# Draft0.net
KiCad netlist of a schematic drawn in EAGLE
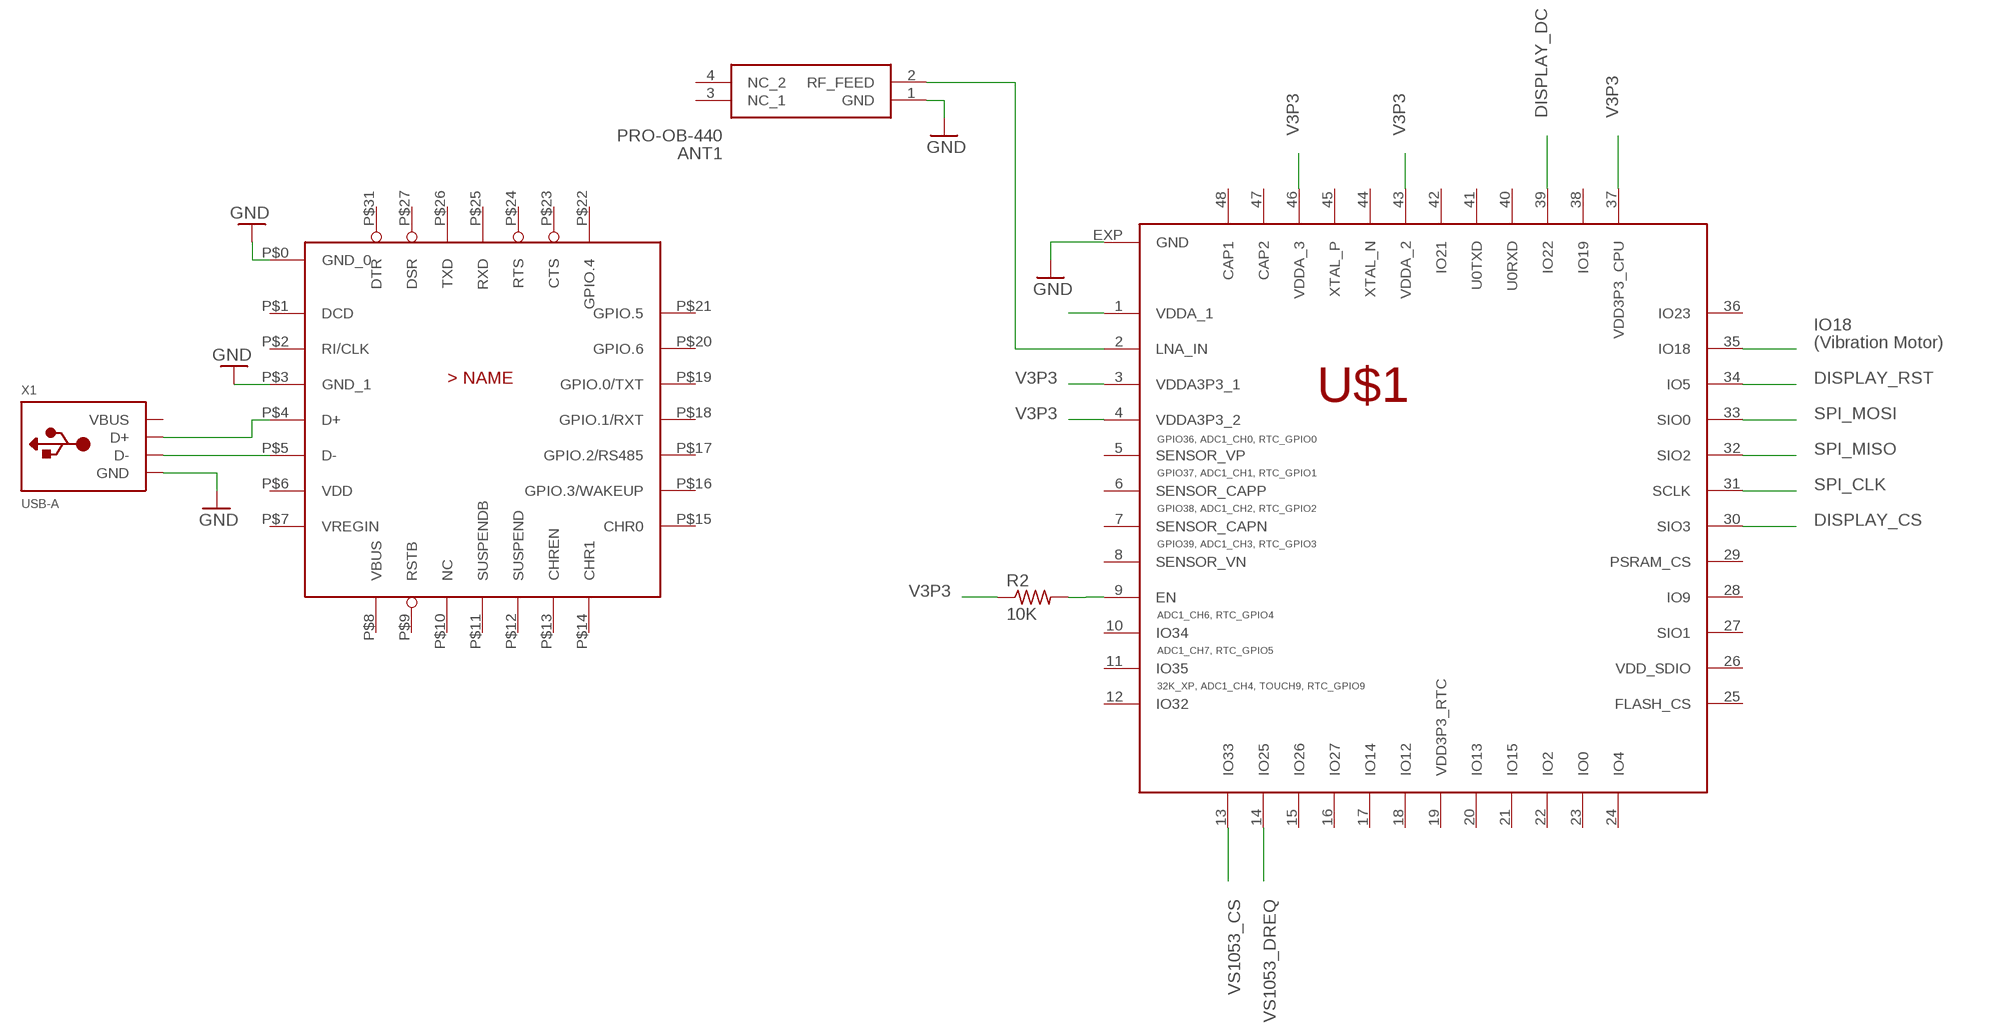
[diagram p0: schematic, sheet 1]
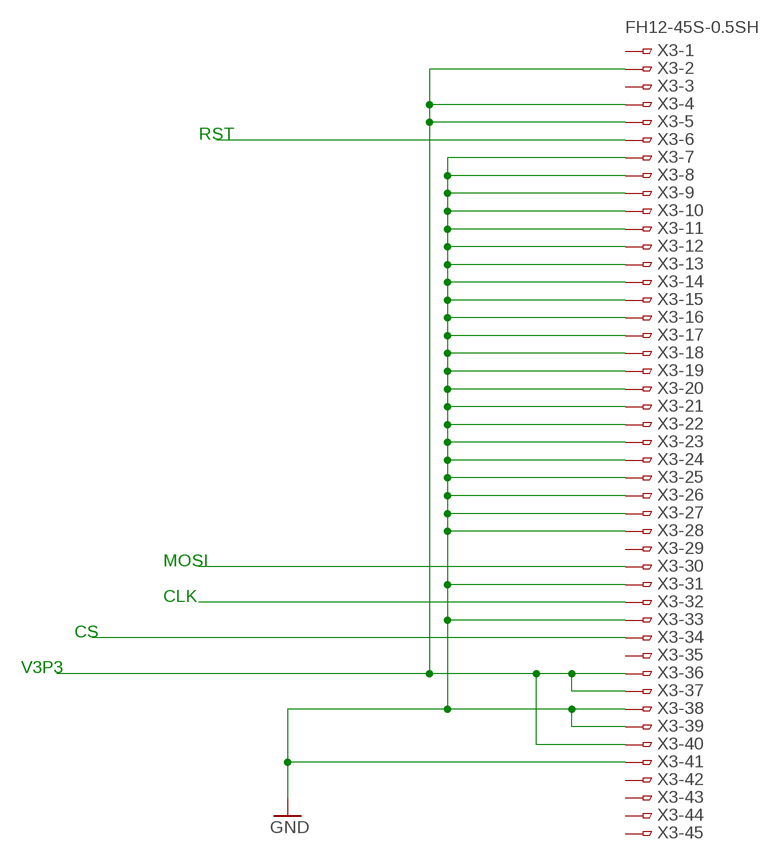
[diagram p1: schematic, sheet 2]
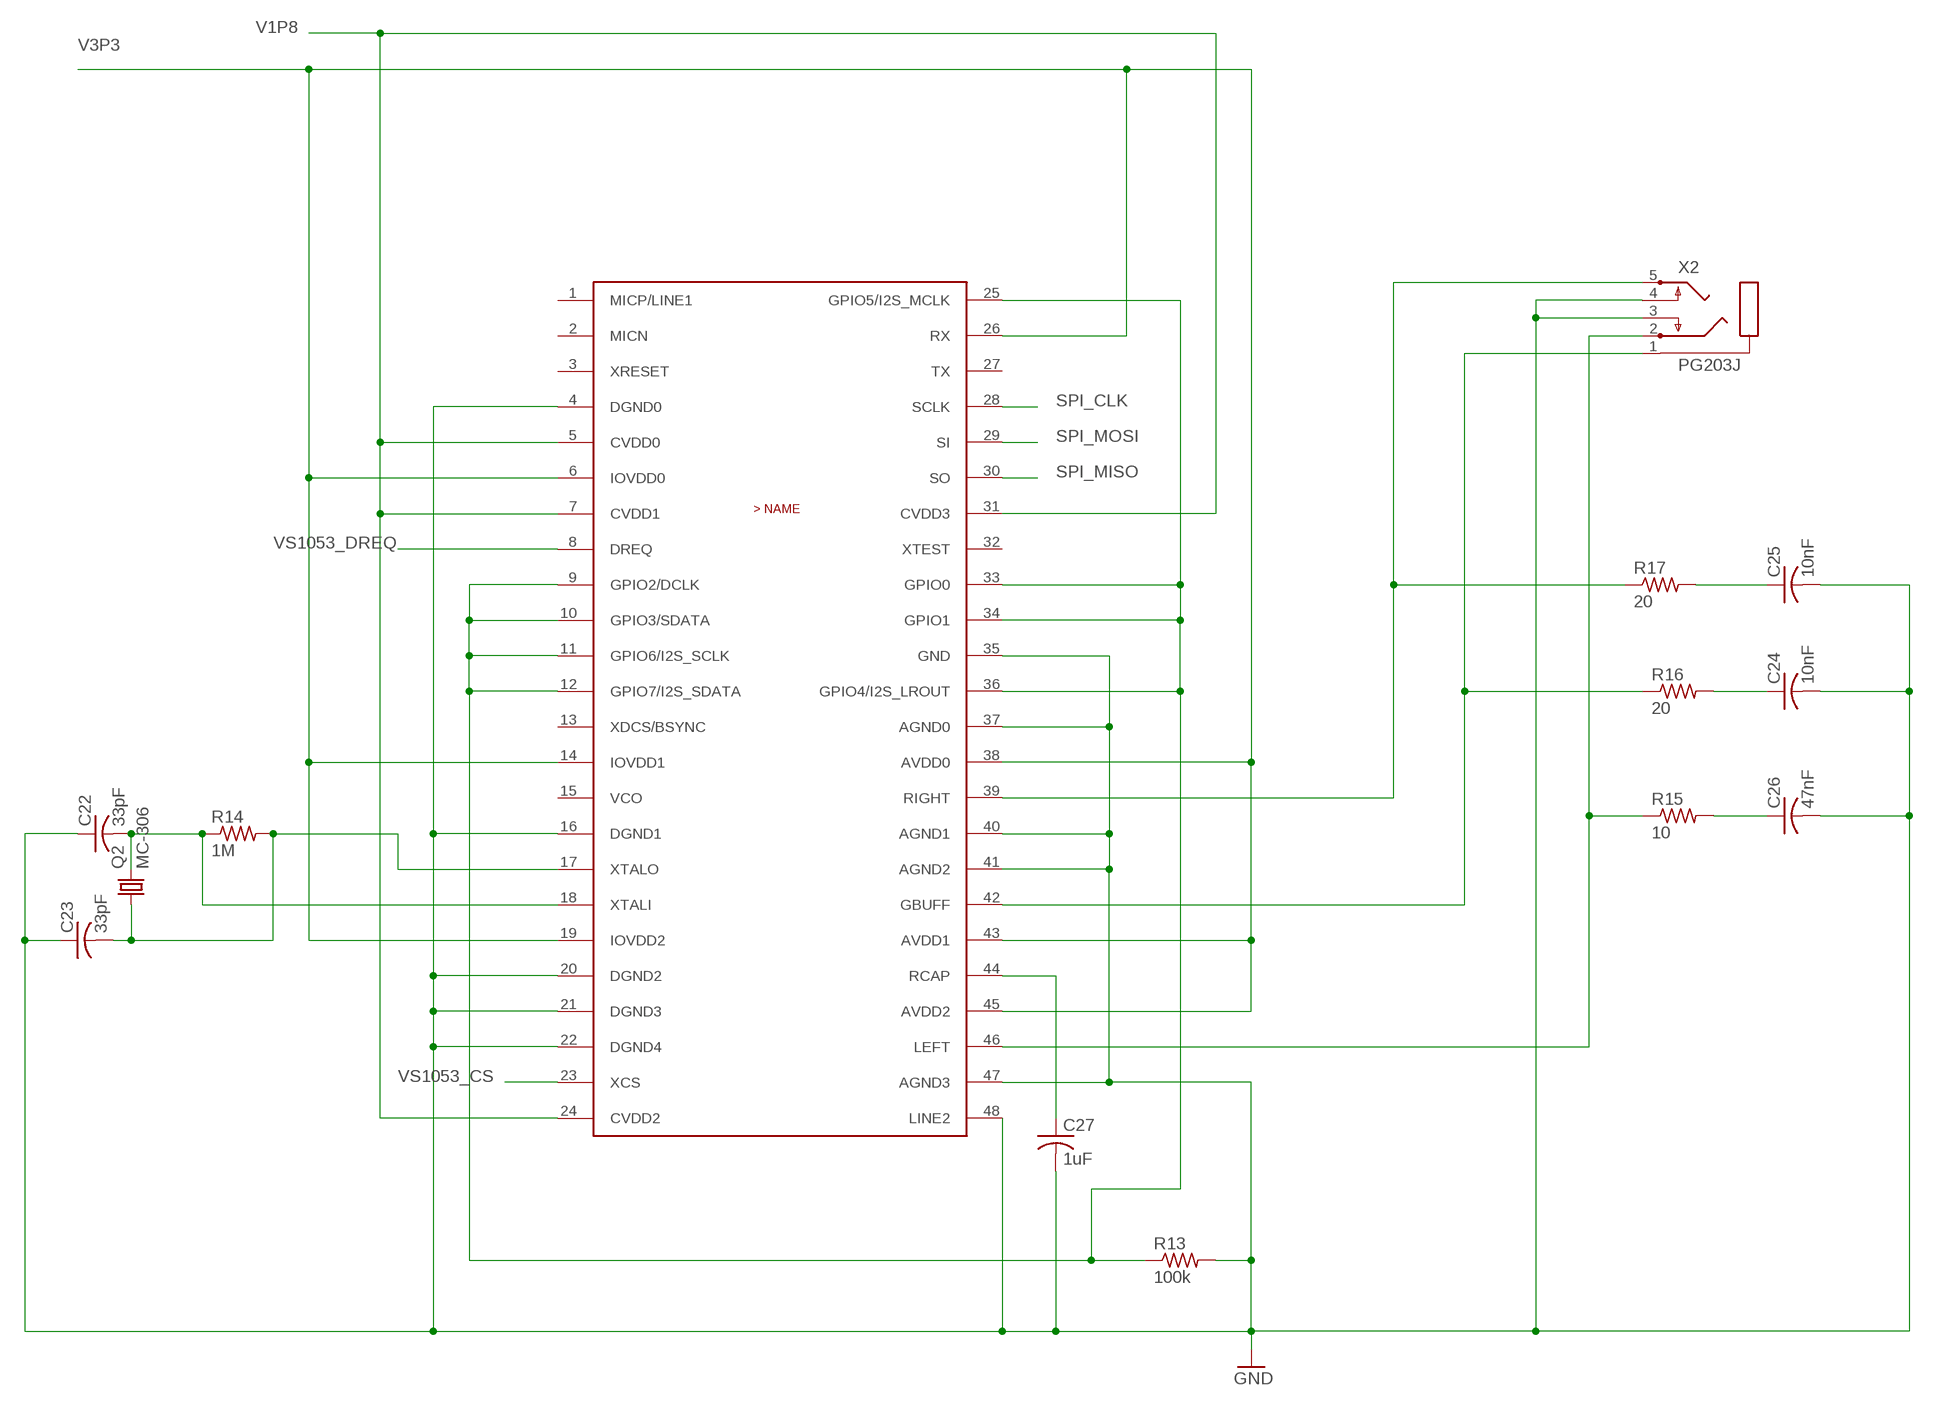
[diagram p2: schematic, sheet 3]
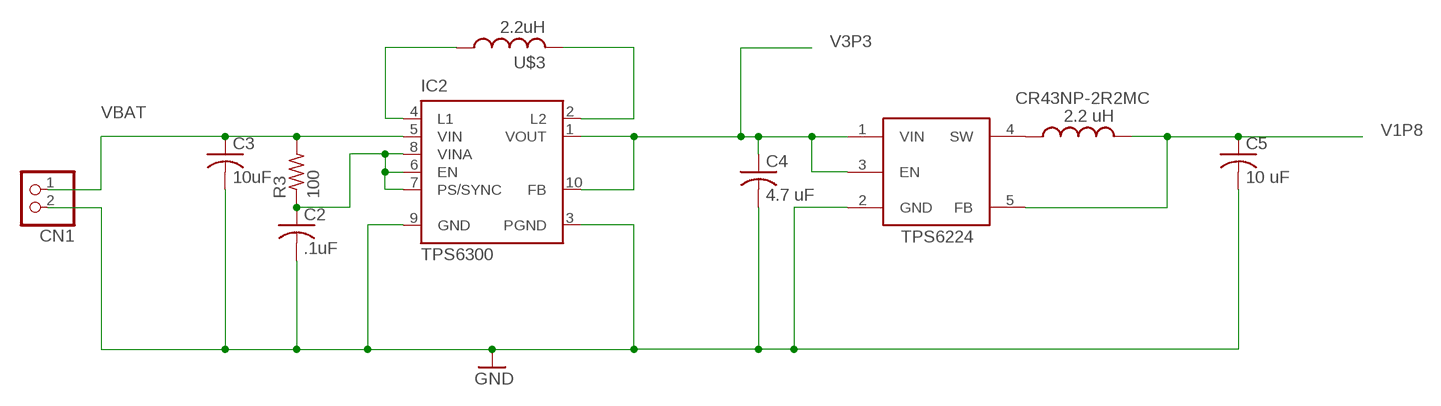
[diagram p3: schematic, sheet 4]
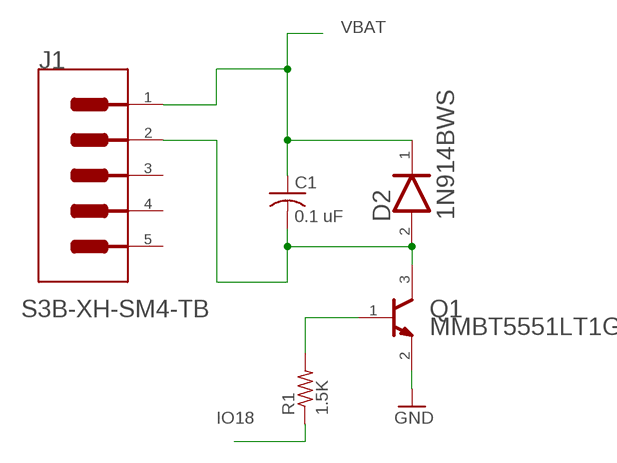
[diagram p4: schematic, sheet 5]
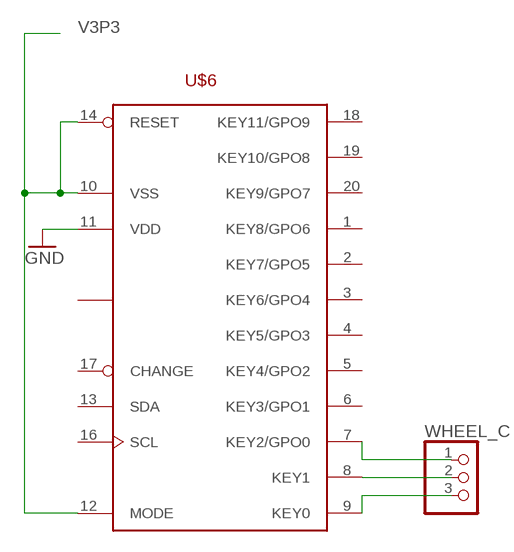
[diagram p5: schematic, sheet 6]

(export (version "E")
  (design (tool "Eeschema 10.0.6"))
  (components
    (comp (ref "U$6")
      (value "COMMS-AT42QT2120XU")
      (footprint "eagle-import:TSSOP20")
      (libsource (lib "eagle-import") (part "COMMS-AT42QT2120XU"))
    )
    (comp (ref "WHEEL_C")
      (value "PINHD-1X3/90")
      (footprint "eagle-import:1X03_90")
      (libsource (lib "eagle-import") (part "PINHD-1X3/90"))
    )
    (comp (ref "C1")
      (value "0.1 uF")
      (footprint "eagle-import:C025-024X044")
      (libsource (lib "eagle-import") (part "C-US025-024X044"))
    )
    (comp (ref "D2")
      (value "ON_SEMI_1N914BWSON_SEMI_1N914BWS_0_0")
      (footprint "eagle-import:ON_SEMI_1N914BWS_0")
      (fields
        (field (name "DIGIKEY_PART_NUMBER") "1N914BWSCT-ND")
        (field (name "MF") "ON Semi")
        (field (name "MOUSER_PART_NUMBER") "512-1N914BWS")
      )
      (libsource (lib "eagle-import") (part "ON_SEMI_1N914BWSON_SEMI_1N914BWS_0_0"))
    )
    (comp (ref "J1")
      (value "JST_S3B-XH-SM4-TBJST_S3B-XH-SM4-TB_0_0")
      (footprint "eagle-import:JST_S3B-XH-SM4-TB_0")
      (fields
        (field (name "DIGIKEY_PART_NUMBER") "455-2263-1-ND")
        (field (name "MF") "JST")
        (field (name "MPN") "S3B-XH-SM4-TB")
      )
      (libsource (lib "eagle-import") (part "JST_S3B-XH-SM4-TBJST_S3B-XH-SM4-TB_0_0"))
    )
    (comp (ref "Q1")
      (value "ON_SEMI_MMBT5551LT1GON_SEMI_MMBT5551LT1G_0_0")
      (footprint "eagle-import:ON_SEMI_MMBT5551LT1G_0")
      (fields
        (field (name "3DS_PART_NUMBER") "452-00001")
        (field (name "DIGIKEY_PART_NUMBER") "MMBT5551LT1GOSCT-ND")
        (field (name "MF") "ON Semi")
      )
      (libsource (lib "eagle-import") (part "ON_SEMI_MMBT5551LT1GON_SEMI_MMBT5551LT1G_0_0"))
    )
    (comp (ref "R1")
      (value "1.5K")
      (footprint "eagle-import:R0603")
      (libsource (lib "eagle-import") (part "R-US_R0603"))
    )
    (comp (ref "ANT1")
      (value "PRO-OB-440")
      (footprint "eagle-import:PRO-OB-440_1")
      (libsource (lib "eagle-import") (part "PRO-OB-440"))
    )
    (comp (ref "R2")
      (value "10K")
      (footprint "eagle-import:M1206")
      (libsource (lib "eagle-import") (part "resistor_348_R-US_M1206"))
    )
    (comp (ref "U$1")
      (value "ESP32-PICO-D4")
      (footprint "eagle-import:QFN48")
      (libsource (lib "eagle-import") (part "ESP32-PICO-D4"))
    )
    (comp (ref "U$4")
      (value "CP2102N-A02-GQFN28")
      (footprint "eagle-import:QFN28")
      (libsource (lib "eagle-import") (part "CP2102N-A02-GQFN28"))
    )
    (comp (ref "X1")
      (value "USB-A")
      (footprint "eagle-import:MOLEX_480371000")
      (libsource (lib "eagle-import") (part "USB-A"))
    )
    (comp (ref "C2")
      (value ".1uF")
      (footprint "eagle-import:C0603")
      (libsource (lib "eagle-import") (part "rcl_334_C-USC0603"))
    )
    (comp (ref "C3")
      (value "10uF")
      (footprint "eagle-import:C0603")
      (libsource (lib "eagle-import") (part "rcl_334_C-USC0603"))
    )
    (comp (ref "C4")
      (value "4.7 uF")
      (footprint "eagle-import:C0805")
      (libsource (lib "eagle-import") (part "rcl_334_C-USC0805"))
    )
    (comp (ref "C5")
      (value "10 uF")
      (footprint "eagle-import:C1210")
      (libsource (lib "eagle-import") (part "rcl_334_C-USC1210"))
    )
    (comp (ref "CN1")
      (value "JST_2PIN-SMT-RA")
      (footprint "eagle-import:JST-PH-2-SMT-RA")
      (libsource (lib "eagle-import") (part "JST_2PIN-SMT-RA"))
    )
    (comp (ref "IC2")
      (value "TPS6300")
      (footprint "eagle-import:DRC-S-PVSON-N10")
      (fields (field (name "MPN") "TPS63000DRCTG4"))
      (libsource (lib "eagle-import") (part "TPS6300"))
    )
    (comp (ref "R3")
      (value "100")
      (footprint "eagle-import:R01005")
      (libsource (lib "eagle-import") (part "R-US_01005"))
    )
    (comp (ref "TPS6224")
      (value "TPS62240")
      (footprint "eagle-import:TSP62240")
      (libsource (lib "eagle-import") (part "TPS62240"))
    )
    (comp (ref "U$3")
      (value "2.2uH")
      (footprint "eagle-import:INDUCTOR")
      (libsource (lib "eagle-import") (part "VLS4012"))
    )
    (comp (ref "U$5")
      (value "CR43NP-2R2MC")
      (footprint "eagle-import:INDUCTOR")
      (libsource (lib "eagle-import") (part "CR43NP-2R2MC"))
    )
    (comp (ref "C22")
      (value "33pF")
      (footprint "eagle-import:C0402")
      (libsource (lib "eagle-import") (part "rcl_334_C-USC0402"))
    )
    (comp (ref "C23")
      (value "33pF")
      (footprint "eagle-import:C0402")
      (libsource (lib "eagle-import") (part "rcl_334_C-USC0402"))
    )
    (comp (ref "C24")
      (value "10nF")
      (footprint "eagle-import:C0201")
      (libsource (lib "eagle-import") (part "C-USC0201"))
    )
    (comp (ref "C25")
      (value "10nF")
      (footprint "eagle-import:C0201")
      (libsource (lib "eagle-import") (part "C-USC0201"))
    )
    (comp (ref "C26")
      (value "47nF")
      (footprint "eagle-import:C0201")
      (libsource (lib "eagle-import") (part "C-USC0201"))
    )
    (comp (ref "C27")
      (value "1uF")
      (footprint "eagle-import:C0201")
      (libsource (lib "eagle-import") (part "C-USC0201"))
    )
    (comp (ref "Q2")
      (value "MC-306")
      (footprint "eagle-import:MC-306")
      (fields (field (name "MPN") "MC-306 60.0KHZ  100PPM ,12.5PF"))
      (libsource (lib "eagle-import") (part "MC-306"))
    )
    (comp (ref "R13")
      (value "100k")
      (footprint "eagle-import:1812X7R")
      (libsource (lib "eagle-import") (part "R-US_1812X7R"))
    )
    (comp (ref "R14")
      (value "1M")
      (footprint "eagle-import:1812X7R")
      (libsource (lib "eagle-import") (part "R-US_1812X7R"))
    )
    (comp (ref "R15")
      (value "10")
      (footprint "eagle-import:R01005")
      (libsource (lib "eagle-import") (part "R-US_01005"))
    )
    (comp (ref "R16")
      (value "20")
      (footprint "eagle-import:R01005")
      (libsource (lib "eagle-import") (part "R-US_01005"))
    )
    (comp (ref "R17")
      (value "20")
      (footprint "eagle-import:R01005")
      (libsource (lib "eagle-import") (part "R-US_01005"))
    )
    (comp (ref "U$7")
      (value "VS1053")
      (footprint "eagle-import:LQFP48")
      (libsource (lib "eagle-import") (part "VS1053"))
    )
    (comp (ref "X2")
      (value "PG203J")
      (footprint "eagle-import:PG203J")
      (libsource (lib "eagle-import") (part "PG203J"))
    )
    (comp (ref "X3")
      (value "FH12-45S-0.5SH")
      (footprint "eagle-import:FH12-45S-0.5SH")
      (libsource (lib "eagle-import") (part "FH12-45S-0.5SH"))
    )
  )
  (nets
    (net (code "1") (name "DISPLAY_CS") (class "Default")
      (node (ref "U$1") (pin "30") (pinfunction "SIO3_30") (pintype "bidirectional"))
    )
    (net (code "2") (name "DISPLAY_DC") (class "Default")
      (node (ref "U$1") (pin "39") (pinfunction "IO22_39") (pintype "bidirectional"))
    )
    (net (code "3") (name "DISPLAY_RST") (class "Default")
      (node (ref "U$1") (pin "34") (pinfunction "IO5_34") (pintype "bidirectional"))
    )
    (net (code "4") (name "GND") (class "Default")
      (node (ref "ANT1") (pin "1") (pinfunction "GND_1") (pintype "bidirectional"))
      (node (ref "C2") (pin "2") (pinfunction "2_2") (pintype "passive"))
      (node (ref "C22") (pin "1") (pinfunction "1_1") (pintype "passive"))
      (node (ref "C23") (pin "1") (pinfunction "1_1") (pintype "passive"))
      (node (ref "C24") (pin "2") (pinfunction "2_2") (pintype "passive"))
      (node (ref "C25") (pin "2") (pinfunction "2_2") (pintype "passive"))
      (node (ref "C26") (pin "2") (pinfunction "2_2") (pintype "passive"))
      (node (ref "C27") (pin "2") (pinfunction "2_2") (pintype "passive"))
      (node (ref "C3") (pin "2") (pinfunction "2_2") (pintype "passive"))
      (node (ref "C4") (pin "2") (pinfunction "2_2") (pintype "passive"))
      (node (ref "C5") (pin "2") (pinfunction "2_2") (pintype "passive"))
      (node (ref "CN1") (pin "2") (pinfunction "1_2") (pintype "passive"))
      (node (ref "IC2") (pin "3") (pinfunction "PGND_3") (pintype "power_in"))
      (node (ref "IC2") (pin "9") (pinfunction "GND_9") (pintype "power_in"))
      (node (ref "Q1") (pin "2") (pinfunction "EMITTER_2") (pintype "passive"))
      (node (ref "R13") (pin "2") (pinfunction "2_2") (pintype "passive"))
      (node (ref "TPS6224") (pin "2") (pinfunction "GND_2") (pintype "bidirectional"))
      (node (ref "U$1") (pin "EXP") (pinfunction "GND_EXP") (pintype "power_in"))
      (node (ref "U$4") (pin "P$0") (pinfunction "GND_0_P$0") (pintype "power_in"))
      (node (ref "U$4") (pin "P$3") (pinfunction "GND_1_P$3") (pintype "power_in"))
      (node (ref "U$6") (pin "11") (pinfunction "VDD_11") (pintype "power_in"))
      (node (ref "U$7") (pin "16") (pinfunction "DGND1_16") (pintype "bidirectional"))
      (node (ref "U$7") (pin "20") (pinfunction "DGND2_20") (pintype "bidirectional"))
      (node (ref "U$7") (pin "21") (pinfunction "DGND3_21") (pintype "bidirectional"))
      (node (ref "U$7") (pin "22") (pinfunction "DGND4_22") (pintype "bidirectional"))
      (node (ref "U$7") (pin "35") (pinfunction "GND_35") (pintype "bidirectional"))
      (node (ref "U$7") (pin "37") (pinfunction "AGND0_37") (pintype "bidirectional"))
      (node (ref "U$7") (pin "4") (pinfunction "DGND0_4") (pintype "bidirectional"))
      (node (ref "U$7") (pin "40") (pinfunction "AGND1_40") (pintype "bidirectional"))
      (node (ref "U$7") (pin "41") (pinfunction "AGND2_41") (pintype "bidirectional"))
      (node (ref "U$7") (pin "47") (pinfunction "AGND3_47") (pintype "bidirectional"))
      (node (ref "U$7") (pin "48") (pinfunction "LINE2_48") (pintype "bidirectional"))
      (node (ref "X1") (pin "4") (pinfunction "GND_4") (pintype "power_in"))
      (node (ref "X2") (pin "3") (pinfunction "3_3") (pintype "passive"))
      (node (ref "X2") (pin "4") (pinfunction "4_4") (pintype "passive"))
      (node (ref "X3") (pin "10") (pinfunction "1_10") (pintype "passive"))
      (node (ref "X3") (pin "11") (pinfunction "1_11") (pintype "passive"))
      (node (ref "X3") (pin "12") (pinfunction "1_12") (pintype "passive"))
      (node (ref "X3") (pin "13") (pinfunction "1_13") (pintype "passive"))
      (node (ref "X3") (pin "14") (pinfunction "1_14") (pintype "passive"))
      (node (ref "X3") (pin "15") (pinfunction "1_15") (pintype "passive"))
      (node (ref "X3") (pin "16") (pinfunction "1_16") (pintype "passive"))
      (node (ref "X3") (pin "17") (pinfunction "1_17") (pintype "passive"))
      (node (ref "X3") (pin "18") (pinfunction "1_18") (pintype "passive"))
      (node (ref "X3") (pin "19") (pinfunction "1_19") (pintype "passive"))
      (node (ref "X3") (pin "20") (pinfunction "1_20") (pintype "passive"))
      (node (ref "X3") (pin "21") (pinfunction "1_21") (pintype "passive"))
      (node (ref "X3") (pin "22") (pinfunction "1_22") (pintype "passive"))
      (node (ref "X3") (pin "23") (pinfunction "1_23") (pintype "passive"))
      (node (ref "X3") (pin "24") (pinfunction "1_24") (pintype "passive"))
      (node (ref "X3") (pin "25") (pinfunction "1_25") (pintype "passive"))
      (node (ref "X3") (pin "26") (pinfunction "1_26") (pintype "passive"))
      (node (ref "X3") (pin "27") (pinfunction "1_27") (pintype "passive"))
      (node (ref "X3") (pin "28") (pinfunction "1_28") (pintype "passive"))
      (node (ref "X3") (pin "31") (pinfunction "1_31") (pintype "passive"))
      (node (ref "X3") (pin "33") (pinfunction "1_33") (pintype "passive"))
      (node (ref "X3") (pin "38") (pinfunction "1_38") (pintype "passive"))
      (node (ref "X3") (pin "39") (pinfunction "1_39") (pintype "passive"))
      (node (ref "X3") (pin "41") (pinfunction "1_41") (pintype "passive"))
      (node (ref "X3") (pin "7") (pinfunction "1_7") (pintype "passive"))
      (node (ref "X3") (pin "8") (pinfunction "1_8") (pintype "passive"))
      (node (ref "X3") (pin "9") (pinfunction "1_9") (pintype "passive"))
    )
    (net (code "5") (name "IO18") (class "Default")
      (node (ref "R1") (pin "1") (pinfunction "1_1") (pintype "passive"))
      (node (ref "U$1") (pin "35") (pinfunction "IO18_35") (pintype "bidirectional"))
    )
    (net (code "6") (name "Net-(ANT1-RF_FEED)") (class "Default")
      (node (ref "ANT1") (pin "2") (pinfunction "RF_FEED_2") (pintype "bidirectional"))
      (node (ref "U$1") (pin "2") (pinfunction "LNA_IN_2") (pintype "bidirectional"))
    )
    (net (code "7") (name "Net-(C24-Pad1)") (class "Default")
      (node (ref "C24") (pin "1") (pinfunction "1_1") (pintype "passive"))
      (node (ref "R16") (pin "2") (pinfunction "2_2") (pintype "passive"))
    )
    (net (code "8") (name "Net-(C25-Pad1)") (class "Default")
      (node (ref "C25") (pin "1") (pinfunction "1_1") (pintype "passive"))
      (node (ref "R17") (pin "2") (pinfunction "2_2") (pintype "passive"))
    )
    (net (code "9") (name "Net-(C26-Pad1)") (class "Default")
      (node (ref "C26") (pin "1") (pinfunction "1_1") (pintype "passive"))
      (node (ref "R15") (pin "2") (pinfunction "2_2") (pintype "passive"))
    )
    (net (code "10") (name "Net-(D2-ANODE)") (class "Default")
      (node (ref "C1") (pin "2") (pinfunction "2_2") (pintype "passive"))
      (node (ref "D2") (pin "2") (pinfunction "ANODE_2") (pintype "bidirectional"))
      (node (ref "J1") (pin "2") (pinfunction "2_2") (pintype "bidirectional"))
      (node (ref "Q1") (pin "3") (pinfunction "COLLECTOR_3") (pintype "passive"))
    )
    (net (code "11") (name "Net-(IC2A-EN)") (class "Default")
      (node (ref "C2") (pin "1") (pinfunction "1_1") (pintype "passive"))
      (node (ref "IC2") (pin "6") (pinfunction "EN_6") (pintype "input"))
      (node (ref "IC2") (pin "7") (pinfunction "PS/SYNC_7") (pintype "input"))
      (node (ref "IC2") (pin "8") (pinfunction "VINA_8") (pintype "input"))
      (node (ref "R3") (pin "1") (pinfunction "1_1") (pintype "passive"))
    )
    (net (code "12") (name "Net-(IC2A-L1)") (class "Default")
      (node (ref "IC2") (pin "4") (pinfunction "L1_4") (pintype "passive"))
      (node (ref "U$3") (pin "P$1") (pinfunction "1_P$1") (pintype "passive"))
    )
    (net (code "13") (name "Net-(IC2A-L2)") (class "Default")
      (node (ref "IC2") (pin "2") (pinfunction "L2_2") (pintype "passive"))
      (node (ref "U$3") (pin "P$2") (pinfunction "2_P$2") (pintype "passive"))
    )
    (net (code "14") (name "Net-(Q1-BASE)") (class "Default")
      (node (ref "Q1") (pin "1") (pinfunction "BASE_1") (pintype "passive"))
      (node (ref "R1") (pin "2") (pinfunction "2_2") (pintype "passive"))
    )
    (net (code "15") (name "Net-(Q2-2)") (class "Default")
      (node (ref "C22") (pin "2") (pinfunction "2_2") (pintype "passive"))
      (node (ref "Q2") (pin "4") (pinfunction "2_4") (pintype "passive"))
      (node (ref "R14") (pin "1") (pinfunction "1_1") (pintype "passive"))
      (node (ref "U$7") (pin "18") (pinfunction "XTALI_18") (pintype "bidirectional"))
    )
    (net (code "16") (name "Net-(TPS6224-SW)") (class "Default")
      (node (ref "TPS6224") (pin "4") (pinfunction "SW_4") (pintype "bidirectional"))
      (node (ref "U$5") (pin "P$1") (pinfunction "1_P$1") (pintype "passive"))
    )
    (net (code "17") (name "Net-(U$1-EN)") (class "Default")
      (node (ref "R2") (pin "2") (pinfunction "2_2") (pintype "passive"))
      (node (ref "U$1") (pin "9") (pinfunction "EN_9") (pintype "input"))
    )
    (net (code "18") (name "Net-(U$4-D+)") (class "Default")
      (node (ref "U$4") (pin "P$4") (pinfunction "D+_P$4") (pintype "bidirectional"))
      (node (ref "X1") (pin "3") (pinfunction "D+_3") (pintype "bidirectional"))
    )
    (net (code "19") (name "Net-(U$4-D-)") (class "Default")
      (node (ref "U$4") (pin "P$5") (pinfunction "D-_P$5") (pintype "bidirectional"))
      (node (ref "X1") (pin "2") (pinfunction "D-_2") (pintype "bidirectional"))
    )
    (net (code "20") (name "Net-(U$6-KEY0)") (class "Default")
      (node (ref "U$6") (pin "9") (pinfunction "KEY0_9") (pintype "bidirectional"))
      (node (ref "WHEEL_C") (pin "3") (pinfunction "3_3") (pintype "passive"))
    )
    (net (code "21") (name "Net-(U$6-KEY1)") (class "Default")
      (node (ref "U$6") (pin "8") (pinfunction "KEY1_8") (pintype "bidirectional"))
      (node (ref "WHEEL_C") (pin "2") (pinfunction "2_2") (pintype "passive"))
    )
    (net (code "22") (name "Net-(U$6-KEY2{slash}GPO0)") (class "Default")
      (node (ref "U$6") (pin "7") (pinfunction "KEY2/GPO0_7") (pintype "bidirectional"))
      (node (ref "WHEEL_C") (pin "1") (pinfunction "1_1") (pintype "passive"))
    )
    (net (code "23") (name "Net-(U$7-GBUFF)") (class "Default")
      (node (ref "R16") (pin "1") (pinfunction "1_1") (pintype "passive"))
      (node (ref "U$7") (pin "42") (pinfunction "GBUFF_42") (pintype "bidirectional"))
      (node (ref "X2") (pin "1") (pinfunction "1_1") (pintype "passive"))
    )
    (net (code "24") (name "Net-(U$7-GPIO0)") (class "Default")
      (node (ref "R13") (pin "1") (pinfunction "1_1") (pintype "passive"))
      (node (ref "U$7") (pin "10") (pinfunction "GPIO3/SDATA_10") (pintype "bidirectional"))
      (node (ref "U$7") (pin "11") (pinfunction "GPIO6/I2S_SCLK_11") (pintype "bidirectional"))
      (node (ref "U$7") (pin "12") (pinfunction "GPIO7/I2S_SDATA_12") (pintype "bidirectional"))
      (node (ref "U$7") (pin "25") (pinfunction "GPIO5/I2S_MCLK_25") (pintype "bidirectional"))
      (node (ref "U$7") (pin "33") (pinfunction "GPIO0_33") (pintype "bidirectional"))
      (node (ref "U$7") (pin "34") (pinfunction "GPIO1_34") (pintype "bidirectional"))
      (node (ref "U$7") (pin "36") (pinfunction "GPIO4/I2S_LROUT_36") (pintype "bidirectional"))
      (node (ref "U$7") (pin "9") (pinfunction "GPIO2/DCLK_9") (pintype "bidirectional"))
    )
    (net (code "25") (name "Net-(U$7-LEFT)") (class "Default")
      (node (ref "R15") (pin "1") (pinfunction "1_1") (pintype "passive"))
      (node (ref "U$7") (pin "46") (pinfunction "LEFT_46") (pintype "bidirectional"))
      (node (ref "X2") (pin "2") (pinfunction "2_2") (pintype "passive"))
    )
    (net (code "26") (name "Net-(U$7-RCAP)") (class "Default")
      (node (ref "C27") (pin "1") (pinfunction "1_1") (pintype "passive"))
      (node (ref "U$7") (pin "44") (pinfunction "RCAP_44") (pintype "bidirectional"))
    )
    (net (code "27") (name "Net-(U$7-RIGHT)") (class "Default")
      (node (ref "R17") (pin "1") (pinfunction "1_1") (pintype "passive"))
      (node (ref "U$7") (pin "39") (pinfunction "RIGHT_39") (pintype "bidirectional"))
      (node (ref "X2") (pin "5") (pinfunction "5_5") (pintype "passive"))
    )
    (net (code "28") (name "Net-(U$7-XTALO)") (class "Default")
      (node (ref "C23") (pin "2") (pinfunction "2_2") (pintype "passive"))
      (node (ref "Q2") (pin "1") (pinfunction "1_1") (pintype "passive"))
      (node (ref "R14") (pin "2") (pinfunction "2_2") (pintype "passive"))
      (node (ref "U$7") (pin "17") (pinfunction "XTALO_17") (pintype "bidirectional"))
    )
    (net (code "29") (name "Net-(X3AD-1)") (class "Default")
      (node (ref "X3") (pin "2") (pinfunction "1_2") (pintype "passive"))
      (node (ref "X3") (pin "36") (pinfunction "1_36") (pintype "passive"))
      (node (ref "X3") (pin "37") (pinfunction "1_37") (pintype "passive"))
      (node (ref "X3") (pin "4") (pinfunction "1_4") (pintype "passive"))
      (node (ref "X3") (pin "40") (pinfunction "1_40") (pintype "passive"))
      (node (ref "X3") (pin "5") (pinfunction "1_5") (pintype "passive"))
    )
    (net (code "30") (name "SPI_CLK") (class "Default")
      (node (ref "U$1") (pin "31") (pinfunction "SCLK_31") (pintype "bidirectional"))
      (node (ref "U$7") (pin "28") (pinfunction "SCLK_28") (pintype "bidirectional"))
    )
    (net (code "31") (name "SPI_MISO") (class "Default")
      (node (ref "U$1") (pin "32") (pinfunction "SIO2_32") (pintype "bidirectional"))
      (node (ref "U$7") (pin "30") (pinfunction "SO_30") (pintype "bidirectional"))
    )
    (net (code "32") (name "SPI_MOSI") (class "Default")
      (node (ref "U$1") (pin "33") (pinfunction "SIO0_33") (pintype "bidirectional"))
      (node (ref "U$7") (pin "29") (pinfunction "SI_29") (pintype "bidirectional"))
    )
    (net (code "33") (name "V1P8") (class "Default")
      (node (ref "C5") (pin "1") (pinfunction "1_1") (pintype "passive"))
      (node (ref "TPS6224") (pin "5") (pinfunction "FB_5") (pintype "bidirectional"))
      (node (ref "U$5") (pin "P$2") (pinfunction "2_P$2") (pintype "passive"))
      (node (ref "U$7") (pin "24") (pinfunction "CVDD2_24") (pintype "bidirectional"))
      (node (ref "U$7") (pin "31") (pinfunction "CVDD3_31") (pintype "bidirectional"))
      (node (ref "U$7") (pin "5") (pinfunction "CVDD0_5") (pintype "bidirectional"))
      (node (ref "U$7") (pin "7") (pinfunction "CVDD1_7") (pintype "bidirectional"))
    )
    (net (code "34") (name "V3P3") (class "Default")
      (node (ref "C4") (pin "1") (pinfunction "1_1") (pintype "passive"))
      (node (ref "IC2") (pin "1") (pinfunction "VOUT_1") (pintype "output"))
      (node (ref "IC2") (pin "10") (pinfunction "FB_10") (pintype "input"))
      (node (ref "R2") (pin "1") (pinfunction "1_1") (pintype "passive"))
      (node (ref "TPS6224") (pin "1") (pinfunction "VIN_1") (pintype "bidirectional"))
      (node (ref "TPS6224") (pin "3") (pinfunction "EN_3") (pintype "bidirectional"))
      (node (ref "U$1") (pin "3") (pinfunction "VDDA3P3_1_3") (pintype "power_in"))
      (node (ref "U$1") (pin "37") (pinfunction "VDD3P3_CPU_37") (pintype "power_in"))
      (node (ref "U$1") (pin "4") (pinfunction "VDDA3P3_2_4") (pintype "power_in"))
      (node (ref "U$1") (pin "43") (pinfunction "VDDA_2_43") (pintype "power_in"))
      (node (ref "U$1") (pin "46") (pinfunction "VDDA_3_46") (pintype "power_in"))
      (node (ref "U$6") (pin "10") (pinfunction "VSS_10") (pintype "power_in"))
      (node (ref "U$6") (pin "12") (pinfunction "MODE_12") (pintype "input"))
      (node (ref "U$6") (pin "14") (pinfunction "RESET_14") (pintype "input"))
      (node (ref "U$7") (pin "14") (pinfunction "IOVDD1_14") (pintype "bidirectional"))
      (node (ref "U$7") (pin "19") (pinfunction "IOVDD2_19") (pintype "bidirectional"))
      (node (ref "U$7") (pin "26") (pinfunction "RX_26") (pintype "bidirectional"))
      (node (ref "U$7") (pin "38") (pinfunction "AVDD0_38") (pintype "bidirectional"))
      (node (ref "U$7") (pin "43") (pinfunction "AVDD1_43") (pintype "bidirectional"))
      (node (ref "U$7") (pin "45") (pinfunction "AVDD2_45") (pintype "bidirectional"))
      (node (ref "U$7") (pin "6") (pinfunction "IOVDD0_6") (pintype "bidirectional"))
    )
    (net (code "35") (name "VBAT") (class "Default")
      (node (ref "C1") (pin "1") (pinfunction "1_1") (pintype "passive"))
      (node (ref "C3") (pin "1") (pinfunction "1_1") (pintype "passive"))
      (node (ref "CN1") (pin "1") (pinfunction "2_1") (pintype "passive"))
      (node (ref "D2") (pin "1") (pinfunction "CATHODE_1") (pintype "bidirectional"))
      (node (ref "IC2") (pin "5") (pinfunction "VIN_5") (pintype "input"))
      (node (ref "J1") (pin "1") (pinfunction "1_1") (pintype "bidirectional"))
      (node (ref "R3") (pin "2") (pinfunction "2_2") (pintype "passive"))
    )
    (net (code "36") (name "VBUS") (class "Default")
      (node (ref "X1") (pin "1") (pinfunction "VBUS_1") (pintype "power_in"))
    )
    (net (code "37") (name "VDD") (class "Default")
      (node (ref "U$4") (pin "P$6") (pinfunction "VDD_P$6") (pintype "power_in"))
    )
    (net (code "38") (name "VDD3P3_RTC") (class "Default")
      (node (ref "U$1") (pin "19") (pinfunction "VDD3P3_RTC_19") (pintype "power_in"))
    )
    (net (code "39") (name "VDD_SDIO") (class "Default")
      (node (ref "U$1") (pin "26") (pinfunction "VDD_SDIO_26") (pintype "power_in"))
    )
    (net (code "40") (name "VREGIN") (class "Default")
      (node (ref "U$4") (pin "P$7") (pinfunction "VREGIN_P$7") (pintype "power_in"))
    )
    (net (code "41") (name "VS1053_CS") (class "Default")
      (node (ref "U$1") (pin "13") (pinfunction "IO33_13") (pintype "bidirectional"))
      (node (ref "U$7") (pin "23") (pinfunction "XCS_23") (pintype "bidirectional"))
    )
    (net (code "42") (name "VS1053_DREQ") (class "Default")
      (node (ref "U$1") (pin "14") (pinfunction "IO25_14") (pintype "bidirectional"))
      (node (ref "U$7") (pin "8") (pinfunction "DREQ_8") (pintype "bidirectional"))
    )
    (net (code "43") (name "unconnected-(ANT1-NC_1-Pad3)") (class "Default")
      (node (ref "ANT1") (pin "3") (pinfunction "NC_1_3") (pintype "bidirectional"))
    )
    (net (code "44") (name "unconnected-(ANT1-NC_2-Pad4)") (class "Default")
      (node (ref "ANT1") (pin "4") (pinfunction "NC_2_4") (pintype "bidirectional"))
    )
    (net (code "45") (name "unconnected-(J1-MNT_1-Pad4)") (class "Default")
      (node (ref "J1") (pin "4") (pinfunction "MNT_1_4") (pintype "bidirectional"))
    )
    (net (code "46") (name "unconnected-(J1-MNT_2-Pad5)") (class "Default")
      (node (ref "J1") (pin "5") (pinfunction "MNT_2_5") (pintype "bidirectional"))
    )
    (net (code "47") (name "unconnected-(J1-Pad3)") (class "Default")
      (node (ref "J1") (pin "3") (pinfunction "3_3") (pintype "bidirectional"))
    )
    (net (code "48") (name "unconnected-(U$1-CAP1-Pad48)") (class "Default")
      (node (ref "U$1") (pin "48") (pinfunction "CAP1_48") (pintype "no_connect"))
    )
    (net (code "49") (name "unconnected-(U$1-CAP2-Pad47)") (class "Default")
      (node (ref "U$1") (pin "47") (pinfunction "CAP2_47") (pintype "no_connect"))
    )
    (net (code "50") (name "unconnected-(U$1-FLASH_CS-Pad25)") (class "Default")
      (node (ref "U$1") (pin "25") (pinfunction "FLASH_CS_25") (pintype "bidirectional"))
    )
    (net (code "51") (name "unconnected-(U$1-IO0-Pad23)") (class "Default")
      (node (ref "U$1") (pin "23") (pinfunction "IO0_23") (pintype "bidirectional"))
    )
    (net (code "52") (name "unconnected-(U$1-IO2-Pad22)") (class "Default")
      (node (ref "U$1") (pin "22") (pinfunction "IO2_22") (pintype "bidirectional"))
    )
    (net (code "53") (name "unconnected-(U$1-IO4-Pad24)") (class "Default")
      (node (ref "U$1") (pin "24") (pinfunction "IO4_24") (pintype "bidirectional"))
    )
    (net (code "54") (name "unconnected-(U$1-IO9-Pad28)") (class "Default")
      (node (ref "U$1") (pin "28") (pinfunction "IO9_28") (pintype "bidirectional"))
    )
    (net (code "55") (name "unconnected-(U$1-IO12-Pad18)") (class "Default")
      (node (ref "U$1") (pin "18") (pinfunction "IO12_18") (pintype "bidirectional"))
    )
    (net (code "56") (name "unconnected-(U$1-IO13-Pad20)") (class "Default")
      (node (ref "U$1") (pin "20") (pinfunction "IO13_20") (pintype "bidirectional"))
    )
    (net (code "57") (name "unconnected-(U$1-IO14-Pad17)") (class "Default")
      (node (ref "U$1") (pin "17") (pinfunction "IO14_17") (pintype "bidirectional"))
    )
    (net (code "58") (name "unconnected-(U$1-IO15-Pad21)") (class "Default")
      (node (ref "U$1") (pin "21") (pinfunction "IO15_21") (pintype "bidirectional"))
    )
    (net (code "59") (name "unconnected-(U$1-IO19-Pad38)") (class "Default")
      (node (ref "U$1") (pin "38") (pinfunction "IO19_38") (pintype "bidirectional"))
    )
    (net (code "60") (name "unconnected-(U$1-IO21-Pad42)") (class "Default")
      (node (ref "U$1") (pin "42") (pinfunction "IO21_42") (pintype "bidirectional"))
    )
    (net (code "61") (name "unconnected-(U$1-IO23-Pad36)") (class "Default")
      (node (ref "U$1") (pin "36") (pinfunction "IO23_36") (pintype "bidirectional"))
    )
    (net (code "62") (name "unconnected-(U$1-IO26-Pad15)") (class "Default")
      (node (ref "U$1") (pin "15") (pinfunction "IO26_15") (pintype "bidirectional"))
    )
    (net (code "63") (name "unconnected-(U$1-IO27-Pad16)") (class "Default")
      (node (ref "U$1") (pin "16") (pinfunction "IO27_16") (pintype "bidirectional"))
    )
    (net (code "64") (name "unconnected-(U$1-IO32-Pad12)") (class "Default")
      (node (ref "U$1") (pin "12") (pinfunction "IO32_12") (pintype "bidirectional"))
    )
    (net (code "65") (name "unconnected-(U$1-IO34-Pad10)") (class "Default")
      (node (ref "U$1") (pin "10") (pinfunction "IO34_10") (pintype "input"))
    )
    (net (code "66") (name "unconnected-(U$1-IO35-Pad11)") (class "Default")
      (node (ref "U$1") (pin "11") (pinfunction "IO35_11") (pintype "input"))
    )
    (net (code "67") (name "unconnected-(U$1-PSRAM_CS-Pad29)") (class "Default")
      (node (ref "U$1") (pin "29") (pinfunction "PSRAM_CS_29") (pintype "bidirectional"))
    )
    (net (code "68") (name "unconnected-(U$1-SENSOR_CAPN-Pad7)") (class "Default")
      (node (ref "U$1") (pin "7") (pinfunction "SENSOR_CAPN_7") (pintype "input"))
    )
    (net (code "69") (name "unconnected-(U$1-SENSOR_CAPP-Pad6)") (class "Default")
      (node (ref "U$1") (pin "6") (pinfunction "SENSOR_CAPP_6") (pintype "input"))
    )
    (net (code "70") (name "unconnected-(U$1-SENSOR_VN-Pad8)") (class "Default")
      (node (ref "U$1") (pin "8") (pinfunction "SENSOR_VN_8") (pintype "input"))
    )
    (net (code "71") (name "unconnected-(U$1-SENSOR_VP-Pad5)") (class "Default")
      (node (ref "U$1") (pin "5") (pinfunction "SENSOR_VP_5") (pintype "input"))
    )
    (net (code "72") (name "unconnected-(U$1-SIO1-Pad27)") (class "Default")
      (node (ref "U$1") (pin "27") (pinfunction "SIO1_27") (pintype "bidirectional"))
    )
    (net (code "73") (name "unconnected-(U$1-U0RXD-Pad40)") (class "Default")
      (node (ref "U$1") (pin "40") (pinfunction "U0RXD_40") (pintype "bidirectional"))
    )
    (net (code "74") (name "unconnected-(U$1-U0TXD-Pad41)") (class "Default")
      (node (ref "U$1") (pin "41") (pinfunction "U0TXD_41") (pintype "bidirectional"))
    )
    (net (code "75") (name "unconnected-(U$1-VDDA_1-Pad1)") (class "Default")
      (node (ref "U$1") (pin "1") (pinfunction "VDDA_1_1") (pintype "power_in"))
    )
    (net (code "76") (name "unconnected-(U$1-XTAL_N-Pad44)") (class "Default")
      (node (ref "U$1") (pin "44") (pinfunction "XTAL_N_44") (pintype "no_connect"))
    )
    (net (code "77") (name "unconnected-(U$1-XTAL_P-Pad45)") (class "Default")
      (node (ref "U$1") (pin "45") (pinfunction "XTAL_P_45") (pintype "no_connect"))
    )
    (net (code "78") (name "unconnected-(U$4-CHR0-PadP$15)") (class "Default")
      (node (ref "U$4") (pin "P$15") (pinfunction "CHR0_P$15") (pintype "output"))
    )
    (net (code "79") (name "unconnected-(U$4-CHR1-PadP$14)") (class "Default")
      (node (ref "U$4") (pin "P$14") (pinfunction "CHR1_P$14") (pintype "output"))
    )
    (net (code "80") (name "unconnected-(U$4-CHREN-PadP$13)") (class "Default")
      (node (ref "U$4") (pin "P$13") (pinfunction "CHREN_P$13") (pintype "output"))
    )
    (net (code "81") (name "unconnected-(U$4-CTS-PadP$23)") (class "Default")
      (node (ref "U$4") (pin "P$23") (pinfunction "CTS_P$23") (pintype "input"))
    )
    (net (code "82") (name "unconnected-(U$4-DCD-PadP$1)") (class "Default")
      (node (ref "U$4") (pin "P$1") (pinfunction "DCD_P$1") (pintype "input"))
    )
    (net (code "83") (name "unconnected-(U$4-DSR-PadP$27)") (class "Default")
      (node (ref "U$4") (pin "P$27") (pinfunction "DSR_P$27") (pintype "input"))
    )
    (net (code "84") (name "unconnected-(U$4-DTR-PadP$31)") (class "Default")
      (node (ref "U$4") (pin "P$31") (pinfunction "DTR_P$31") (pintype "output"))
    )
    (net (code "85") (name "unconnected-(U$4-GPIO.0{slash}TXT-PadP$19)") (class "Default")
      (node (ref "U$4") (pin "P$19") (pinfunction "GPIO.0/TXT_P$19") (pintype "bidirectional"))
    )
    (net (code "86") (name "unconnected-(U$4-GPIO.1{slash}RXT-PadP$18)") (class "Default")
      (node (ref "U$4") (pin "P$18") (pinfunction "GPIO.1/RXT_P$18") (pintype "bidirectional"))
    )
    (net (code "87") (name "unconnected-(U$4-GPIO.2{slash}RS485-PadP$17)") (class "Default")
      (node (ref "U$4") (pin "P$17") (pinfunction "GPIO.2/RS485_P$17") (pintype "bidirectional"))
    )
    (net (code "88") (name "unconnected-(U$4-GPIO.3{slash}WAKEUP-PadP$16)") (class "Default")
      (node (ref "U$4") (pin "P$16") (pinfunction "GPIO.3/WAKEUP_P$16") (pintype "bidirectional"))
    )
    (net (code "89") (name "unconnected-(U$4-GPIO.4-PadP$22)") (class "Default")
      (node (ref "U$4") (pin "P$22") (pinfunction "GPIO.4_P$22") (pintype "bidirectional"))
    )
    (net (code "90") (name "unconnected-(U$4-GPIO.5-PadP$21)") (class "Default")
      (node (ref "U$4") (pin "P$21") (pinfunction "GPIO.5_P$21") (pintype "bidirectional"))
    )
    (net (code "91") (name "unconnected-(U$4-GPIO.6-PadP$20)") (class "Default")
      (node (ref "U$4") (pin "P$20") (pinfunction "GPIO.6_P$20") (pintype "bidirectional"))
    )
    (net (code "92") (name "unconnected-(U$4-NC-PadP$10)") (class "Default")
      (node (ref "U$4") (pin "P$10") (pinfunction "NC_P$10") (pintype "no_connect"))
    )
    (net (code "93") (name "unconnected-(U$4-RI{slash}CLK-PadP$2)") (class "Default")
      (node (ref "U$4") (pin "P$2") (pinfunction "RI/CLK_P$2") (pintype "bidirectional"))
    )
    (net (code "94") (name "unconnected-(U$4-RSTB-PadP$9)") (class "Default")
      (node (ref "U$4") (pin "P$9") (pinfunction "RSTB_P$9") (pintype "input"))
    )
    (net (code "95") (name "unconnected-(U$4-RTS-PadP$24)") (class "Default")
      (node (ref "U$4") (pin "P$24") (pinfunction "RTS_P$24") (pintype "output"))
    )
    (net (code "96") (name "unconnected-(U$4-RXD-PadP$25)") (class "Default")
      (node (ref "U$4") (pin "P$25") (pinfunction "RXD_P$25") (pintype "input"))
    )
    (net (code "97") (name "unconnected-(U$4-SUSPEND-PadP$12)") (class "Default")
      (node (ref "U$4") (pin "P$12") (pinfunction "SUSPEND_P$12") (pintype "output"))
    )
    (net (code "98") (name "unconnected-(U$4-SUSPENDB-PadP$11)") (class "Default")
      (node (ref "U$4") (pin "P$11") (pinfunction "SUSPENDB_P$11") (pintype "output"))
    )
    (net (code "99") (name "unconnected-(U$4-TXD-PadP$26)") (class "Default")
      (node (ref "U$4") (pin "P$26") (pinfunction "TXD_P$26") (pintype "output"))
    )
    (net (code "100") (name "unconnected-(U$4-VBUS-PadP$8)") (class "Default")
      (node (ref "U$4") (pin "P$8") (pinfunction "VBUS_P$8") (pintype "input"))
    )
    (net (code "101") (name "unconnected-(U$6-CHANGE-Pad17)") (class "Default")
      (node (ref "U$6") (pin "17") (pinfunction "CHANGE_17") (pintype "open_collector"))
    )
    (net (code "102") (name "unconnected-(U$6-KEY3{slash}GPO1-Pad6)") (class "Default")
      (node (ref "U$6") (pin "6") (pinfunction "KEY3/GPO1_6") (pintype "bidirectional"))
    )
    (net (code "103") (name "unconnected-(U$6-KEY4{slash}GPO2-Pad5)") (class "Default")
      (node (ref "U$6") (pin "5") (pinfunction "KEY4/GPO2_5") (pintype "bidirectional"))
    )
    (net (code "104") (name "unconnected-(U$6-KEY5{slash}GPO3-Pad4)") (class "Default")
      (node (ref "U$6") (pin "4") (pinfunction "KEY5/GPO3_4") (pintype "bidirectional"))
    )
    (net (code "105") (name "unconnected-(U$6-KEY6{slash}GPO4-Pad3)") (class "Default")
      (node (ref "U$6") (pin "3") (pinfunction "KEY6/GPO4_3") (pintype "bidirectional"))
    )
    (net (code "106") (name "unconnected-(U$6-KEY7{slash}GPO5-Pad2)") (class "Default")
      (node (ref "U$6") (pin "2") (pinfunction "KEY7/GPO5_2") (pintype "bidirectional"))
    )
    (net (code "107") (name "unconnected-(U$6-KEY8{slash}GPO6-Pad1)") (class "Default")
      (node (ref "U$6") (pin "1") (pinfunction "KEY8/GPO6_1") (pintype "bidirectional"))
    )
    (net (code "108") (name "unconnected-(U$6-KEY9{slash}GPO7-Pad20)") (class "Default")
      (node (ref "U$6") (pin "20") (pinfunction "KEY9/GPO7_20") (pintype "bidirectional"))
    )
    (net (code "109") (name "unconnected-(U$6-KEY10{slash}GPO8-Pad19)") (class "Default")
      (node (ref "U$6") (pin "19") (pinfunction "KEY10/GPO8_19") (pintype "bidirectional"))
    )
    (net (code "110") (name "unconnected-(U$6-KEY11{slash}GPO9-Pad18)") (class "Default")
      (node (ref "U$6") (pin "18") (pinfunction "KEY11/GPO9_18") (pintype "bidirectional"))
    )
    (net (code "111") (name "unconnected-(U$6-NC-Pad15)") (class "Default")
      (node (ref "U$6") (pin "15") (pinfunction "NC_15") (pintype "no_connect"))
    )
    (net (code "112") (name "unconnected-(U$6-SCL-Pad16)") (class "Default")
      (node (ref "U$6") (pin "16") (pinfunction "SCL_16") (pintype "open_collector"))
    )
    (net (code "113") (name "unconnected-(U$6-SDA-Pad13)") (class "Default")
      (node (ref "U$6") (pin "13") (pinfunction "SDA_13") (pintype "open_collector"))
    )
    (net (code "114") (name "unconnected-(U$7-MICN-Pad2)") (class "Default")
      (node (ref "U$7") (pin "2") (pinfunction "MICN_2") (pintype "bidirectional"))
    )
    (net (code "115") (name "unconnected-(U$7-MICP{slash}LINE1-Pad1)") (class "Default")
      (node (ref "U$7") (pin "1") (pinfunction "MICP/LINE1_1") (pintype "bidirectional"))
    )
    (net (code "116") (name "unconnected-(U$7-TX-Pad27)") (class "Default")
      (node (ref "U$7") (pin "27") (pinfunction "TX_27") (pintype "bidirectional"))
    )
    (net (code "117") (name "unconnected-(U$7-VCO-Pad15)") (class "Default")
      (node (ref "U$7") (pin "15") (pinfunction "VCO_15") (pintype "bidirectional"))
    )
    (net (code "118") (name "unconnected-(U$7-XDCS{slash}BSYNC-Pad13)") (class "Default")
      (node (ref "U$7") (pin "13") (pinfunction "XDCS/BSYNC_13") (pintype "bidirectional"))
    )
    (net (code "119") (name "unconnected-(U$7-XRESET-Pad3)") (class "Default")
      (node (ref "U$7") (pin "3") (pinfunction "XRESET_3") (pintype "bidirectional"))
    )
    (net (code "120") (name "unconnected-(U$7-XTEST-Pad32)") (class "Default")
      (node (ref "U$7") (pin "32") (pinfunction "XTEST_32") (pintype "bidirectional"))
    )
    (net (code "121") (name "unconnected-(X3-Pad1)") (class "Default")
      (node (ref "X3") (pin "1") (pinfunction "1_1") (pintype "passive"))
    )
    (net (code "122") (name "unconnected-(X3AB-1-Pad34)") (class "Default")
      (node (ref "X3") (pin "34") (pinfunction "1_34") (pintype "passive"))
    )
    (net (code "123") (name "unconnected-(X3AC-1-Pad35)") (class "Default")
      (node (ref "X3") (pin "35") (pinfunction "1_35") (pintype "passive"))
    )
    (net (code "124") (name "unconnected-(X3AK-1-Pad42)") (class "Default")
      (node (ref "X3") (pin "42") (pinfunction "1_42") (pintype "passive"))
    )
    (net (code "125") (name "unconnected-(X3AL-1-Pad43)") (class "Default")
      (node (ref "X3") (pin "43") (pinfunction "1_43") (pintype "passive"))
    )
    (net (code "126") (name "unconnected-(X3AM-1-Pad44)") (class "Default")
      (node (ref "X3") (pin "44") (pinfunction "1_44") (pintype "passive"))
    )
    (net (code "127") (name "unconnected-(X3AN-1-Pad45)") (class "Default")
      (node (ref "X3") (pin "45") (pinfunction "1_45") (pintype "passive"))
    )
    (net (code "128") (name "unconnected-(X3AP-1-Pad6)") (class "Default")
      (node (ref "X3") (pin "6") (pinfunction "1_6") (pintype "passive"))
    )
    (net (code "129") (name "unconnected-(X3V-1-Pad29)") (class "Default")
      (node (ref "X3") (pin "29") (pinfunction "1_29") (pintype "passive"))
    )
    (net (code "130") (name "unconnected-(X3W-1-Pad3)") (class "Default")
      (node (ref "X3") (pin "3") (pinfunction "1_3") (pintype "passive"))
    )
    (net (code "131") (name "unconnected-(X3X-1-Pad30)") (class "Default")
      (node (ref "X3") (pin "30") (pinfunction "1_30") (pintype "passive"))
    )
    (net (code "132") (name "unconnected-(X3Z-1-Pad32)") (class "Default")
      (node (ref "X3") (pin "32") (pinfunction "1_32") (pintype "passive"))
    )
  )
)
